# SATA.net
KiCad netlist of a schematic drawn in Altium Designer
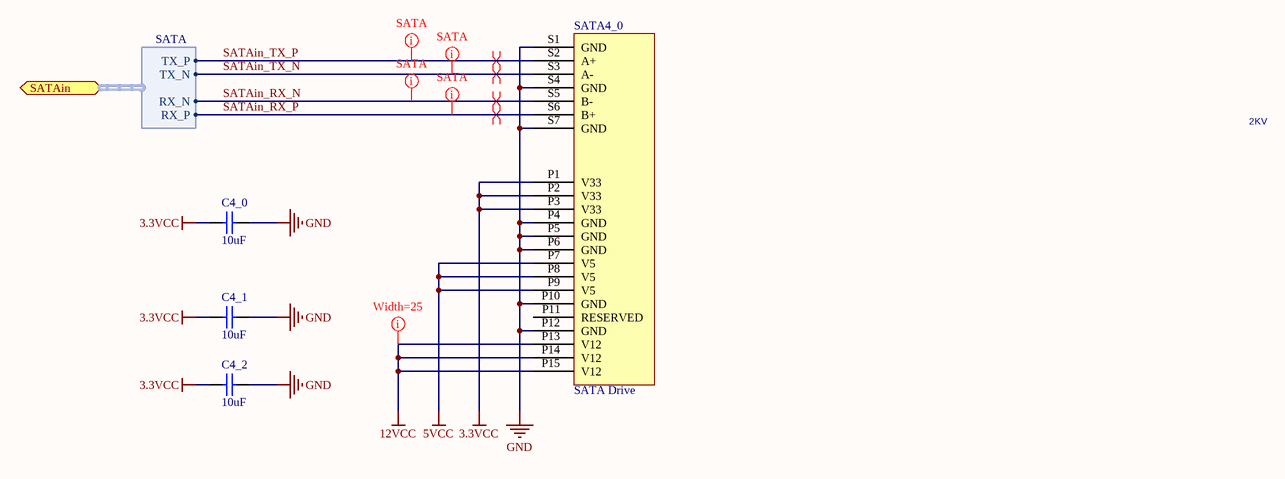
[diagram p0: SATA.SchDoc]

(export (version "E")
  (design (tool "Eeschema 10.0.6"))
  (components
    (comp (ref "C4_0")
      (value "10uF")
      (footprint "PassiveComponents:1210 (3225) Capacitor")
      (description "Capacitor")
      (fields (field (name "DIGIKEY PART NUMBER") "399-1158-1-ND"))
      (libsource (lib "PassiveComponents") (part "Capacitor (non-polarized)"))
    )
    (comp (ref "C4_1")
      (value "10uF")
      (footprint "PassiveComponents:1210 (3225) Capacitor")
      (description "Capacitor")
      (fields (field (name "DIGIKEY PART NUMBER") "399-1158-1-ND"))
      (libsource (lib "PassiveComponents") (part "Capacitor (non-polarized)"))
    )
    (comp (ref "C4_2")
      (value "10uF")
      (footprint "PassiveComponents:1210 (3225) Capacitor")
      (description "Capacitor")
      (fields (field (name "DIGIKEY PART NUMBER") "399-1158-1-ND"))
      (libsource (lib "PassiveComponents") (part "Capacitor (non-polarized)"))
    )
    (comp (ref "SATA4_0")
      (value "SATA Drive")
      (footprint "SDSATAConnectors:SATA HDD")
      (description "SATA HDD, FCI Part# 10029364")
      (fields (field (name "DIGIKEY PART NUMBER") "609-1028-ND"))
      (libsource (lib "SATAConnectors") (part "SATA Drive"))
    )
  )
  (nets
    (net (code "2") (name "/SATAin_RX_N") (class "Default")
      (node (ref "SATA4_0") (pin "S5") (pinfunction "B-_S5") (pintype "passive"))
    )
    (net (code "3") (name "/SATAin_RX_P") (class "Default")
      (node (ref "SATA4_0") (pin "S6") (pinfunction "B+_S6") (pintype "passive"))
    )
    (net (code "4") (name "/SATAin_TX_N") (class "Default")
      (node (ref "SATA4_0") (pin "S3") (pinfunction "A-_S3") (pintype "passive"))
    )
    (net (code "5") (name "/SATAin_TX_P") (class "Default")
      (node (ref "SATA4_0") (pin "S2") (pinfunction "A+_S2") (pintype "passive"))
    )
    (net (code "7") (name "3.3VCC") (class "Default")
      (node (ref "C4_0") (pin "2") (pinfunction "2_2") (pintype "passive"))
      (node (ref "C4_1") (pin "2") (pinfunction "2_2") (pintype "passive"))
      (node (ref "C4_2") (pin "2") (pinfunction "2_2") (pintype "passive"))
      (node (ref "SATA4_0") (pin "P1") (pinfunction "V33_P1") (pintype "passive"))
      (node (ref "SATA4_0") (pin "P2") (pinfunction "V33_P2") (pintype "passive"))
      (node (ref "SATA4_0") (pin "P3") (pinfunction "V33_P3") (pintype "passive"))
    )
    (net (code "8") (name "5VCC") (class "Default")
      (node (ref "SATA4_0") (pin "P7") (pinfunction "V5_P7") (pintype "passive"))
      (node (ref "SATA4_0") (pin "P8") (pinfunction "V5_P8") (pintype "passive"))
      (node (ref "SATA4_0") (pin "P9") (pinfunction "V5_P9") (pintype "passive"))
    )
    (net (code "9") (name "12VCC") (class "Default")
      (node (ref "SATA4_0") (pin "P13") (pinfunction "V12_P13") (pintype "passive"))
      (node (ref "SATA4_0") (pin "P14") (pinfunction "V12_P14") (pintype "passive"))
      (node (ref "SATA4_0") (pin "P15") (pinfunction "V12_P15") (pintype "passive"))
    )
    (net (code "10") (name "GND") (class "Default")
      (node (ref "C4_0") (pin "1") (pinfunction "1_1") (pintype "passive"))
      (node (ref "C4_1") (pin "1") (pinfunction "1_1") (pintype "passive"))
      (node (ref "C4_2") (pin "1") (pinfunction "1_1") (pintype "passive"))
      (node (ref "SATA4_0") (pin "P10") (pinfunction "GND_P10") (pintype "passive"))
      (node (ref "SATA4_0") (pin "P12") (pinfunction "GND_P12") (pintype "passive"))
      (node (ref "SATA4_0") (pin "P4") (pinfunction "GND_P4") (pintype "passive"))
      (node (ref "SATA4_0") (pin "P5") (pinfunction "GND_P5") (pintype "passive"))
      (node (ref "SATA4_0") (pin "P6") (pinfunction "GND_P6") (pintype "passive"))
      (node (ref "SATA4_0") (pin "S1") (pinfunction "GND_S1") (pintype "passive"))
      (node (ref "SATA4_0") (pin "S4") (pinfunction "GND_S4") (pintype "passive"))
      (node (ref "SATA4_0") (pin "S7") (pinfunction "GND_S7") (pintype "passive"))
    )
    (net (code "11") (name "unconnected-(SATA4_0-RESERVED-PadP11)") (class "Default")
      (node (ref "SATA4_0") (pin "P11") (pinfunction "RESERVED_P11") (pintype "passive"))
    )
  )
)
